# MiniAdd-OnV11.net
KiCad netlist of a schematic drawn in EAGLE
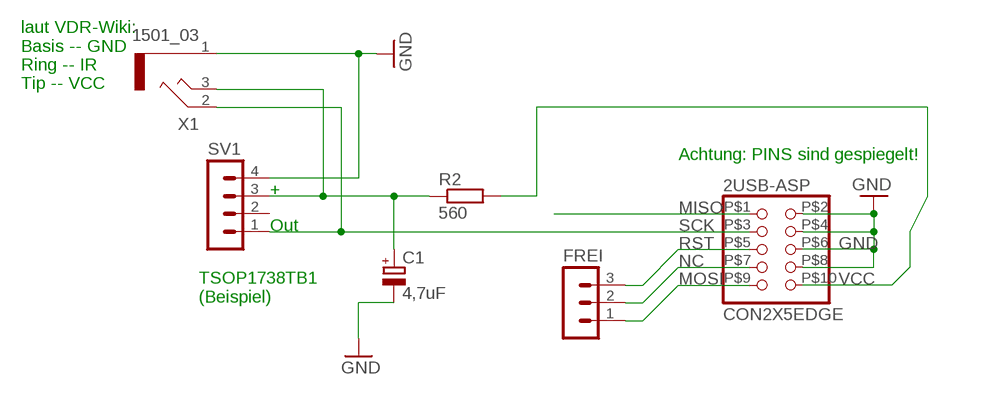
[diagram p0: schematic, sheet 1]

(export (version "E")
  (design (tool "Eeschema 10.0.6"))
  (components
    (comp (ref "2USB-ASP")
      (value "CON2X5EDGE")
      (footprint "eagle-import:CON2X5EDGE")
      (libsource (lib "eagle-import") (part "CON2X5EDGE"))
    )
    (comp (ref "C1")
      (value "4,7uF")
      (footprint "eagle-import:E1,8-4")
      (libsource (lib "eagle-import") (part "CPOL-EUE1.8-4"))
    )
    (comp (ref "FREI")
      (value "MA03-1")
      (footprint "eagle-import:MA03-1")
      (libsource (lib "eagle-import") (part "MA03-1"))
    )
    (comp (ref "R2")
      (value "560")
      (footprint "eagle-import:0204V")
      (libsource (lib "eagle-import") (part "R-EU_0204/2V"))
    )
    (comp (ref "SV1")
      (value "MA04-1")
      (footprint "eagle-import:MA04-1")
      (libsource (lib "eagle-import") (part "MA04-1"))
    )
    (comp (ref "X1")
      (value "1501_03")
      (footprint "eagle-import:1501_03")
      (libsource (lib "eagle-import") (part "1501_03"))
    )
  )
  (nets
    (net (code "1") (name "/MISO") (class "Default")
      (node (ref "2USB-ASP") (pin "P$1") (pinfunction "1_P$1") (pintype "passive"))
    )
    (net (code "2") (name "/MOSI") (class "Default")
      (node (ref "2USB-ASP") (pin "P$9") (pinfunction "9_P$9") (pintype "passive"))
      (node (ref "FREI") (pin "1") (pinfunction "1_1") (pintype "passive"))
    )
    (net (code "3") (name "/NC") (class "Default")
      (node (ref "2USB-ASP") (pin "P$7") (pinfunction "7_P$7") (pintype "passive"))
      (node (ref "FREI") (pin "2") (pinfunction "2_2") (pintype "passive"))
    )
    (net (code "4") (name "/RST") (class "Default")
      (node (ref "2USB-ASP") (pin "P$5") (pinfunction "5_P$5") (pintype "passive"))
      (node (ref "FREI") (pin "3") (pinfunction "3_3") (pintype "passive"))
    )
    (net (code "5") (name "/SCK") (class "Default")
      (node (ref "2USB-ASP") (pin "P$3") (pinfunction "3_P$3") (pintype "passive"))
      (node (ref "SV1") (pin "1") (pinfunction "1_1") (pintype "passive"))
      (node (ref "X1") (pin "2") (pinfunction "2_2") (pintype "passive"))
    )
    (net (code "6") (name "/VCC") (class "Default")
      (node (ref "2USB-ASP") (pin "P$10") (pinfunction "10_P$10") (pintype "passive"))
      (node (ref "R2") (pin "2") (pinfunction "2_2") (pintype "passive"))
    )
    (net (code "7") (name "GND") (class "Default")
      (node (ref "2USB-ASP") (pin "P$2") (pinfunction "2_P$2") (pintype "passive"))
      (node (ref "2USB-ASP") (pin "P$4") (pinfunction "4_P$4") (pintype "passive"))
      (node (ref "2USB-ASP") (pin "P$6") (pinfunction "6_P$6") (pintype "passive"))
      (node (ref "2USB-ASP") (pin "P$8") (pinfunction "8_P$8") (pintype "passive"))
      (node (ref "C1") (pin "-") (pinfunction "-_-") (pintype "passive"))
      (node (ref "SV1") (pin "4") (pinfunction "4_4") (pintype "passive"))
      (node (ref "X1") (pin "1") (pinfunction "1_1") (pintype "passive"))
    )
    (net (code "8") (name "Net-(C1-Pad+)") (class "Default")
      (node (ref "C1") (pin "+") (pinfunction "+_+") (pintype "passive"))
      (node (ref "R2") (pin "1") (pinfunction "1_1") (pintype "passive"))
      (node (ref "SV1") (pin "3") (pinfunction "3_3") (pintype "passive"))
      (node (ref "X1") (pin "3") (pinfunction "3_3") (pintype "passive"))
    )
    (net (code "9") (name "unconnected-(SV1-Pad2)") (class "Default")
      (node (ref "SV1") (pin "2") (pinfunction "2_2") (pintype "passive"))
    )
  )
)
